# BLE_Sensors_LEDs.net
KiCad netlist of a schematic drawn in Altium Designer
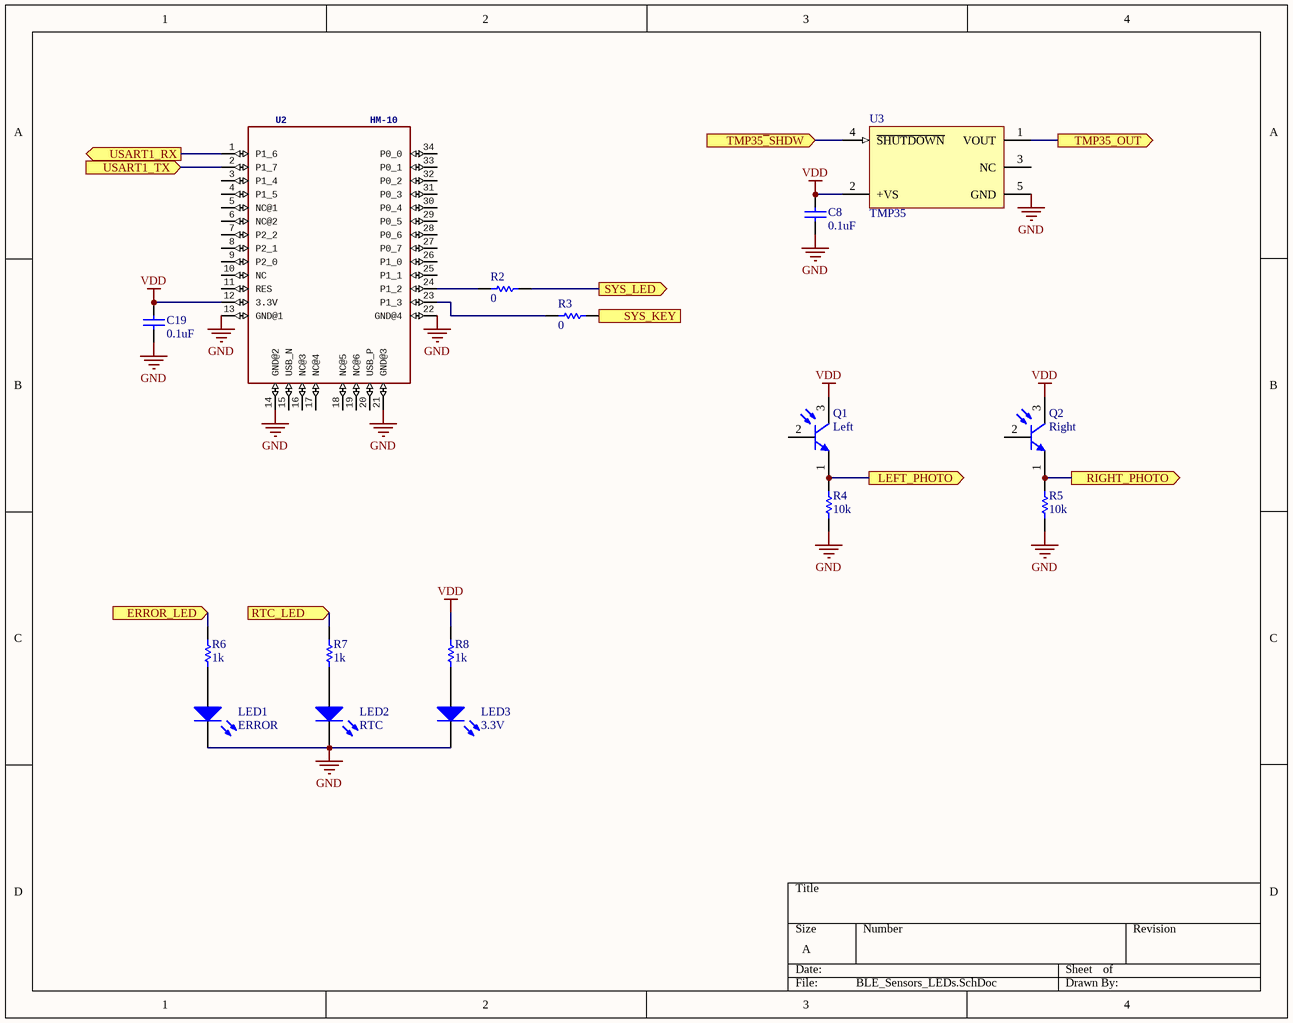
[diagram p0: BLE_Sensors_LEDs.SchDoc]

(export (version "E")
  (design (tool "Eeschema 10.0.6"))
  (components
    (comp (ref "C8")
      (value "0.1uF")
      (footprint "CAPC1608X90X40ML10T20")
      (fields (field (name "TOLERANCE") "±10%") (field (name "MANUFACTURER") "Yageo"))
      (libsource (lib "Altium Content Vault") (part "CAP-NP-2"))
    )
    (comp (ref "C19")
      (value "0.1uF")
      (footprint "CAPC1608X90X40ML10T20")
      (fields (field (name "TOLERANCE") "±10%") (field (name "MANUFACTURER") "Yageo"))
      (libsource (lib "Altium Content Vault") (part "CAP-NP-2"))
    )
    (comp (ref "LED1")
      (value "ERROR")
      (footprint "0805_A")
      (description "SMD mono-color Chip LED, WL-SMCW, Super Red")
      (fields (field (name "MANUFACTURER") "Wuerth Elektronik") (field (name "PARTNUMBER") "150080SS75000"))
      (libsource (lib "Altium Content Vault") (part "WE-LED_K1A2-2"))
    )
    (comp (ref "LED2")
      (value "RTC")
      (footprint "0805_A")
      (description "SMD mono-color Chip LED, WL-SMCW, Super Red")
      (fields (field (name "MANUFACTURER") "Wuerth Elektronik") (field (name "PARTNUMBER") "150080SS75000"))
      (libsource (lib "Altium Content Vault") (part "WE-LED_K1A2-2"))
    )
    (comp (ref "LED3")
      (value "3.3V")
      (footprint "0805_A")
      (description "SMD mono-color Chip LED, WL-SMCW, Super Red")
      (fields (field (name "MANUFACTURER") "Wuerth Elektronik") (field (name "PARTNUMBER") "150080SS75000"))
      (libsource (lib "Altium Content Vault") (part "WE-LED_K1A2-2"))
    )
    (comp (ref "Q1")
      (value "Left")
      (footprint "VSIL-TEMT6000X01_V")
      (description "Ambient Light Sensor\r\n, 100 mW, -40 to 100 degC, 3-Pin SMD, RoHS, Tape and Reel")
      (libsource (lib "VFD_Clock_lib") (part "CMP-1666-00035-1"))
    )
    (comp (ref "Q2")
      (value "Right")
      (footprint "VSIL-TEMT6000X01_V")
      (description "Ambient Light Sensor\r\n, 100 mW, -40 to 100 degC, 3-Pin SMD, RoHS, Tape and Reel")
      (libsource (lib "VFD_Clock_lib") (part "CMP-1666-00035-1"))
    )
    (comp (ref "R2")
      (value "0")
      (footprint "RESC2013X50X30LL20T20")
      (fields (field (name "MANUFACTURER") "Vishay Dale") (field (name "PART NUMBER") "CRCW08050000Z0EA"))
      (libsource (lib "Altium Content Vault") (part "RES"))
    )
    (comp (ref "R3")
      (value "0")
      (footprint "RESC2013X50X30LL20T20")
      (fields (field (name "MANUFACTURER") "Vishay Dale") (field (name "PART NUMBER") "CRCW08050000Z0EA"))
      (libsource (lib "Altium Content Vault") (part "RES"))
    )
    (comp (ref "R4")
      (value "10k")
      (footprint "RESC1608X55X30LL15T15")
      (fields (field (name "PART NUMBER") "ERJ-3EKF1002V") (field (name "MANUFACTURER") "Panasonic"))
      (libsource (lib "Altium Content Vault") (part "RES"))
    )
    (comp (ref "R5")
      (value "10k")
      (footprint "RESC1608X55X30LL15T15")
      (fields (field (name "PART NUMBER") "ERJ-3EKF1002V") (field (name "MANUFACTURER") "Panasonic"))
      (libsource (lib "Altium Content Vault") (part "RES"))
    )
    (comp (ref "R6")
      (value "1k")
      (footprint "RESC1608X55X30LL20T20")
      (fields (field (name "MANUFACTURER") "Panasonic") (field (name "PART NUMBER") "ERA3AEB102V"))
      (libsource (lib "Altium Content Vault") (part "RES"))
    )
    (comp (ref "R7")
      (value "1k")
      (footprint "RESC1608X55X30LL20T20")
      (fields (field (name "MANUFACTURER") "Panasonic") (field (name "PART NUMBER") "ERA3AEB102V"))
      (libsource (lib "Altium Content Vault") (part "RES"))
    )
    (comp (ref "R8")
      (value "1k")
      (footprint "RESC1608X55X30LL20T20")
      (fields (field (name "MANUFACTURER") "Panasonic") (field (name "PART NUMBER") "ERA3AEB102V"))
      (libsource (lib "Altium Content Vault") (part "RES"))
    )
    (comp (ref "U2") (value "HM-10") (footprint "HM-10") (libsource (lib "HM-10_BLE") (part "HM-10")))
    (comp (ref "U3")
      (value "TMP35")
      (footprint "ADI-RJ-5_M")
      (description "Voltage Output Temperature Sensor, 2.7 to 5.5 V Supply, Industrial, 5-pin SOT23 (RJ-5), Reel")
      (fields (field (name "PARTNUMBER") "TMP35GRTZ-REEL7") (field (name "MANUFACTURER") "Analog Devices"))
      (libsource (lib "VFD_Clock_lib") (part "CMP-0887-00046-1"))
    )
  )
  (nets
    (net (code "1") (name "/ERROR_LED") (class "Default")
      (node (ref "R6") (pin "2") (pinfunction "2_2") (pintype "passive"))
    )
    (net (code "2") (name "/LEFT_PHOTO") (class "Default")
      (node (ref "Q1") (pin "1") (pinfunction "E_1") (pintype "passive"))
      (node (ref "R4") (pin "2") (pinfunction "2_2") (pintype "passive"))
    )
    (net (code "3") (name "/RIGHT_PHOTO") (class "Default")
      (node (ref "Q2") (pin "1") (pinfunction "E_1") (pintype "passive"))
      (node (ref "R5") (pin "2") (pinfunction "2_2") (pintype "passive"))
    )
    (net (code "4") (name "/RTC_LED") (class "Default")
      (node (ref "R7") (pin "2") (pinfunction "2_2") (pintype "passive"))
    )
    (net (code "5") (name "/SYS_KEY") (class "Default")
      (node (ref "R3") (pin "2") (pinfunction "2_2") (pintype "passive"))
    )
    (net (code "6") (name "/SYS_LED") (class "Default")
      (node (ref "R2") (pin "2") (pinfunction "2_2") (pintype "passive"))
    )
    (net (code "7") (name "/TMP35_OUT") (class "Default")
      (node (ref "U3") (pin "1") (pinfunction "VOUT_1") (pintype "tri_state"))
    )
    (net (code "8") (name "/TMP35~{_}SHDW") (class "Default")
      (node (ref "U3") (pin "4") (pinfunction "~{SHUTDOWN}_4") (pintype "input"))
    )
    (net (code "9") (name "/USART1_RX") (class "Default")
      (node (ref "U2") (pin "1") (pinfunction "P1_6_1") (pintype "bidirectional"))
    )
    (net (code "10") (name "/USART1_TX") (class "Default")
      (node (ref "U2") (pin "2") (pinfunction "P1_7_2") (pintype "bidirectional"))
    )
    (net (code "11") (name "GND") (class "Default")
      (node (ref "C19") (pin "1") (pinfunction "1_1") (pintype "passive"))
      (node (ref "C8") (pin "1") (pinfunction "1_1") (pintype "passive"))
      (node (ref "LED1") (pin "1") (pinfunction "K_1") (pintype "passive"))
      (node (ref "LED2") (pin "1") (pinfunction "K_1") (pintype "passive"))
      (node (ref "LED3") (pin "1") (pinfunction "K_1") (pintype "passive"))
      (node (ref "R4") (pin "1") (pinfunction "1_1") (pintype "passive"))
      (node (ref "R5") (pin "1") (pinfunction "1_1") (pintype "passive"))
      (node (ref "U2") (pin "13") (pinfunction "GND@1_13") (pintype "bidirectional"))
      (node (ref "U2") (pin "14") (pinfunction "GND@2_14") (pintype "bidirectional"))
      (node (ref "U2") (pin "21") (pinfunction "GND@3_21") (pintype "bidirectional"))
      (node (ref "U2") (pin "22") (pinfunction "GND@4_22") (pintype "bidirectional"))
      (node (ref "U3") (pin "5") (pinfunction "GND_5") (pintype "power_in"))
    )
    (net (code "12") (name "Net-(LED1-A)") (class "Default")
      (node (ref "LED1") (pin "2") (pinfunction "A_2") (pintype "passive"))
      (node (ref "R6") (pin "1") (pinfunction "1_1") (pintype "passive"))
    )
    (net (code "13") (name "Net-(LED2-A)") (class "Default")
      (node (ref "LED2") (pin "2") (pinfunction "A_2") (pintype "passive"))
      (node (ref "R7") (pin "1") (pinfunction "1_1") (pintype "passive"))
    )
    (net (code "14") (name "Net-(LED3-A)") (class "Default")
      (node (ref "LED3") (pin "2") (pinfunction "A_2") (pintype "passive"))
      (node (ref "R8") (pin "1") (pinfunction "1_1") (pintype "passive"))
    )
    (net (code "15") (name "Net-(U2-P1_2)") (class "Default")
      (node (ref "R2") (pin "1") (pinfunction "1_1") (pintype "passive"))
      (node (ref "U2") (pin "24") (pinfunction "P1_2_24") (pintype "bidirectional"))
    )
    (net (code "16") (name "Net-(U2-P1_3)") (class "Default")
      (node (ref "R3") (pin "1") (pinfunction "1_1") (pintype "passive"))
      (node (ref "U2") (pin "23") (pinfunction "P1_3_23") (pintype "bidirectional"))
    )
    (net (code "17") (name "VDD") (class "Default")
      (node (ref "C19") (pin "2") (pinfunction "2_2") (pintype "passive"))
      (node (ref "C8") (pin "2") (pinfunction "2_2") (pintype "passive"))
      (node (ref "Q1") (pin "3") (pinfunction "C_3") (pintype "passive"))
      (node (ref "Q2") (pin "3") (pinfunction "C_3") (pintype "passive"))
      (node (ref "R8") (pin "2") (pinfunction "2_2") (pintype "passive"))
      (node (ref "U2") (pin "12") (pinfunction "3.3V_12") (pintype "bidirectional"))
      (node (ref "U3") (pin "2") (pinfunction "+VS_2") (pintype "power_in"))
    )
    (net (code "18") (name "unconnected-(Q1-B-Pad2)") (class "Default")
      (node (ref "Q1") (pin "2") (pinfunction "B_2") (pintype "passive"))
    )
    (net (code "19") (name "unconnected-(Q2-B-Pad2)") (class "Default")
      (node (ref "Q2") (pin "2") (pinfunction "B_2") (pintype "passive"))
    )
    (net (code "20") (name "unconnected-(U2-NC-Pad10)") (class "Default")
      (node (ref "U2") (pin "10") (pinfunction "NC_10") (pintype "bidirectional"))
    )
    (net (code "21") (name "unconnected-(U2-NC@1-Pad5)") (class "Default")
      (node (ref "U2") (pin "5") (pinfunction "NC@1_5") (pintype "bidirectional"))
    )
    (net (code "22") (name "unconnected-(U2-NC@2-Pad6)") (class "Default")
      (node (ref "U2") (pin "6") (pinfunction "NC@2_6") (pintype "bidirectional"))
    )
    (net (code "23") (name "unconnected-(U2-NC@3-Pad16)") (class "Default")
      (node (ref "U2") (pin "16") (pinfunction "NC@3_16") (pintype "bidirectional"))
    )
    (net (code "24") (name "unconnected-(U2-NC@4-Pad17)") (class "Default")
      (node (ref "U2") (pin "17") (pinfunction "NC@4_17") (pintype "bidirectional"))
    )
    (net (code "25") (name "unconnected-(U2-NC@5-Pad18)") (class "Default")
      (node (ref "U2") (pin "18") (pinfunction "NC@5_18") (pintype "bidirectional"))
    )
    (net (code "26") (name "unconnected-(U2-NC@6-Pad19)") (class "Default")
      (node (ref "U2") (pin "19") (pinfunction "NC@6_19") (pintype "bidirectional"))
    )
    (net (code "27") (name "unconnected-(U2-P0_0-Pad34)") (class "Default")
      (node (ref "U2") (pin "34") (pinfunction "P0_0_34") (pintype "bidirectional"))
    )
    (net (code "28") (name "unconnected-(U2-P0_1-Pad33)") (class "Default")
      (node (ref "U2") (pin "33") (pinfunction "P0_1_33") (pintype "bidirectional"))
    )
    (net (code "29") (name "unconnected-(U2-P0_2-Pad32)") (class "Default")
      (node (ref "U2") (pin "32") (pinfunction "P0_2_32") (pintype "bidirectional"))
    )
    (net (code "30") (name "unconnected-(U2-P0_3-Pad31)") (class "Default")
      (node (ref "U2") (pin "31") (pinfunction "P0_3_31") (pintype "bidirectional"))
    )
    (net (code "31") (name "unconnected-(U2-P0_4-Pad30)") (class "Default")
      (node (ref "U2") (pin "30") (pinfunction "P0_4_30") (pintype "bidirectional"))
    )
    (net (code "32") (name "unconnected-(U2-P0_5-Pad29)") (class "Default")
      (node (ref "U2") (pin "29") (pinfunction "P0_5_29") (pintype "bidirectional"))
    )
    (net (code "33") (name "unconnected-(U2-P0_6-Pad28)") (class "Default")
      (node (ref "U2") (pin "28") (pinfunction "P0_6_28") (pintype "bidirectional"))
    )
    (net (code "34") (name "unconnected-(U2-P0_7-Pad27)") (class "Default")
      (node (ref "U2") (pin "27") (pinfunction "P0_7_27") (pintype "bidirectional"))
    )
    (net (code "35") (name "unconnected-(U2-P1_0-Pad26)") (class "Default")
      (node (ref "U2") (pin "26") (pinfunction "P1_0_26") (pintype "bidirectional"))
    )
    (net (code "36") (name "unconnected-(U2-P1_1-Pad25)") (class "Default")
      (node (ref "U2") (pin "25") (pinfunction "P1_1_25") (pintype "bidirectional"))
    )
    (net (code "37") (name "unconnected-(U2-P1_4-Pad3)") (class "Default")
      (node (ref "U2") (pin "3") (pinfunction "P1_4_3") (pintype "bidirectional"))
    )
    (net (code "38") (name "unconnected-(U2-P1_5-Pad4)") (class "Default")
      (node (ref "U2") (pin "4") (pinfunction "P1_5_4") (pintype "bidirectional"))
    )
    (net (code "39") (name "unconnected-(U2-P2_0-Pad9)") (class "Default")
      (node (ref "U2") (pin "9") (pinfunction "P2_0_9") (pintype "bidirectional"))
    )
    (net (code "40") (name "unconnected-(U2-P2_1-Pad8)") (class "Default")
      (node (ref "U2") (pin "8") (pinfunction "P2_1_8") (pintype "bidirectional"))
    )
    (net (code "41") (name "unconnected-(U2-P2_2-Pad7)") (class "Default")
      (node (ref "U2") (pin "7") (pinfunction "P2_2_7") (pintype "bidirectional"))
    )
    (net (code "42") (name "unconnected-(U2-RES-Pad11)") (class "Default")
      (node (ref "U2") (pin "11") (pinfunction "RES_11") (pintype "bidirectional"))
    )
    (net (code "43") (name "unconnected-(U2-USB_N-Pad15)") (class "Default")
      (node (ref "U2") (pin "15") (pinfunction "USB_N_15") (pintype "bidirectional"))
    )
    (net (code "44") (name "unconnected-(U2-USB_P-Pad20)") (class "Default")
      (node (ref "U2") (pin "20") (pinfunction "USB_P_20") (pintype "bidirectional"))
    )
    (net (code "45") (name "unconnected-(U3-NC-Pad3)") (class "Default")
      (node (ref "U3") (pin "3") (pinfunction "NC_3") (pintype "passive"))
    )
  )
)
